# NT_SolarModule2.net
KiCad netlist of a schematic drawn in EAGLE
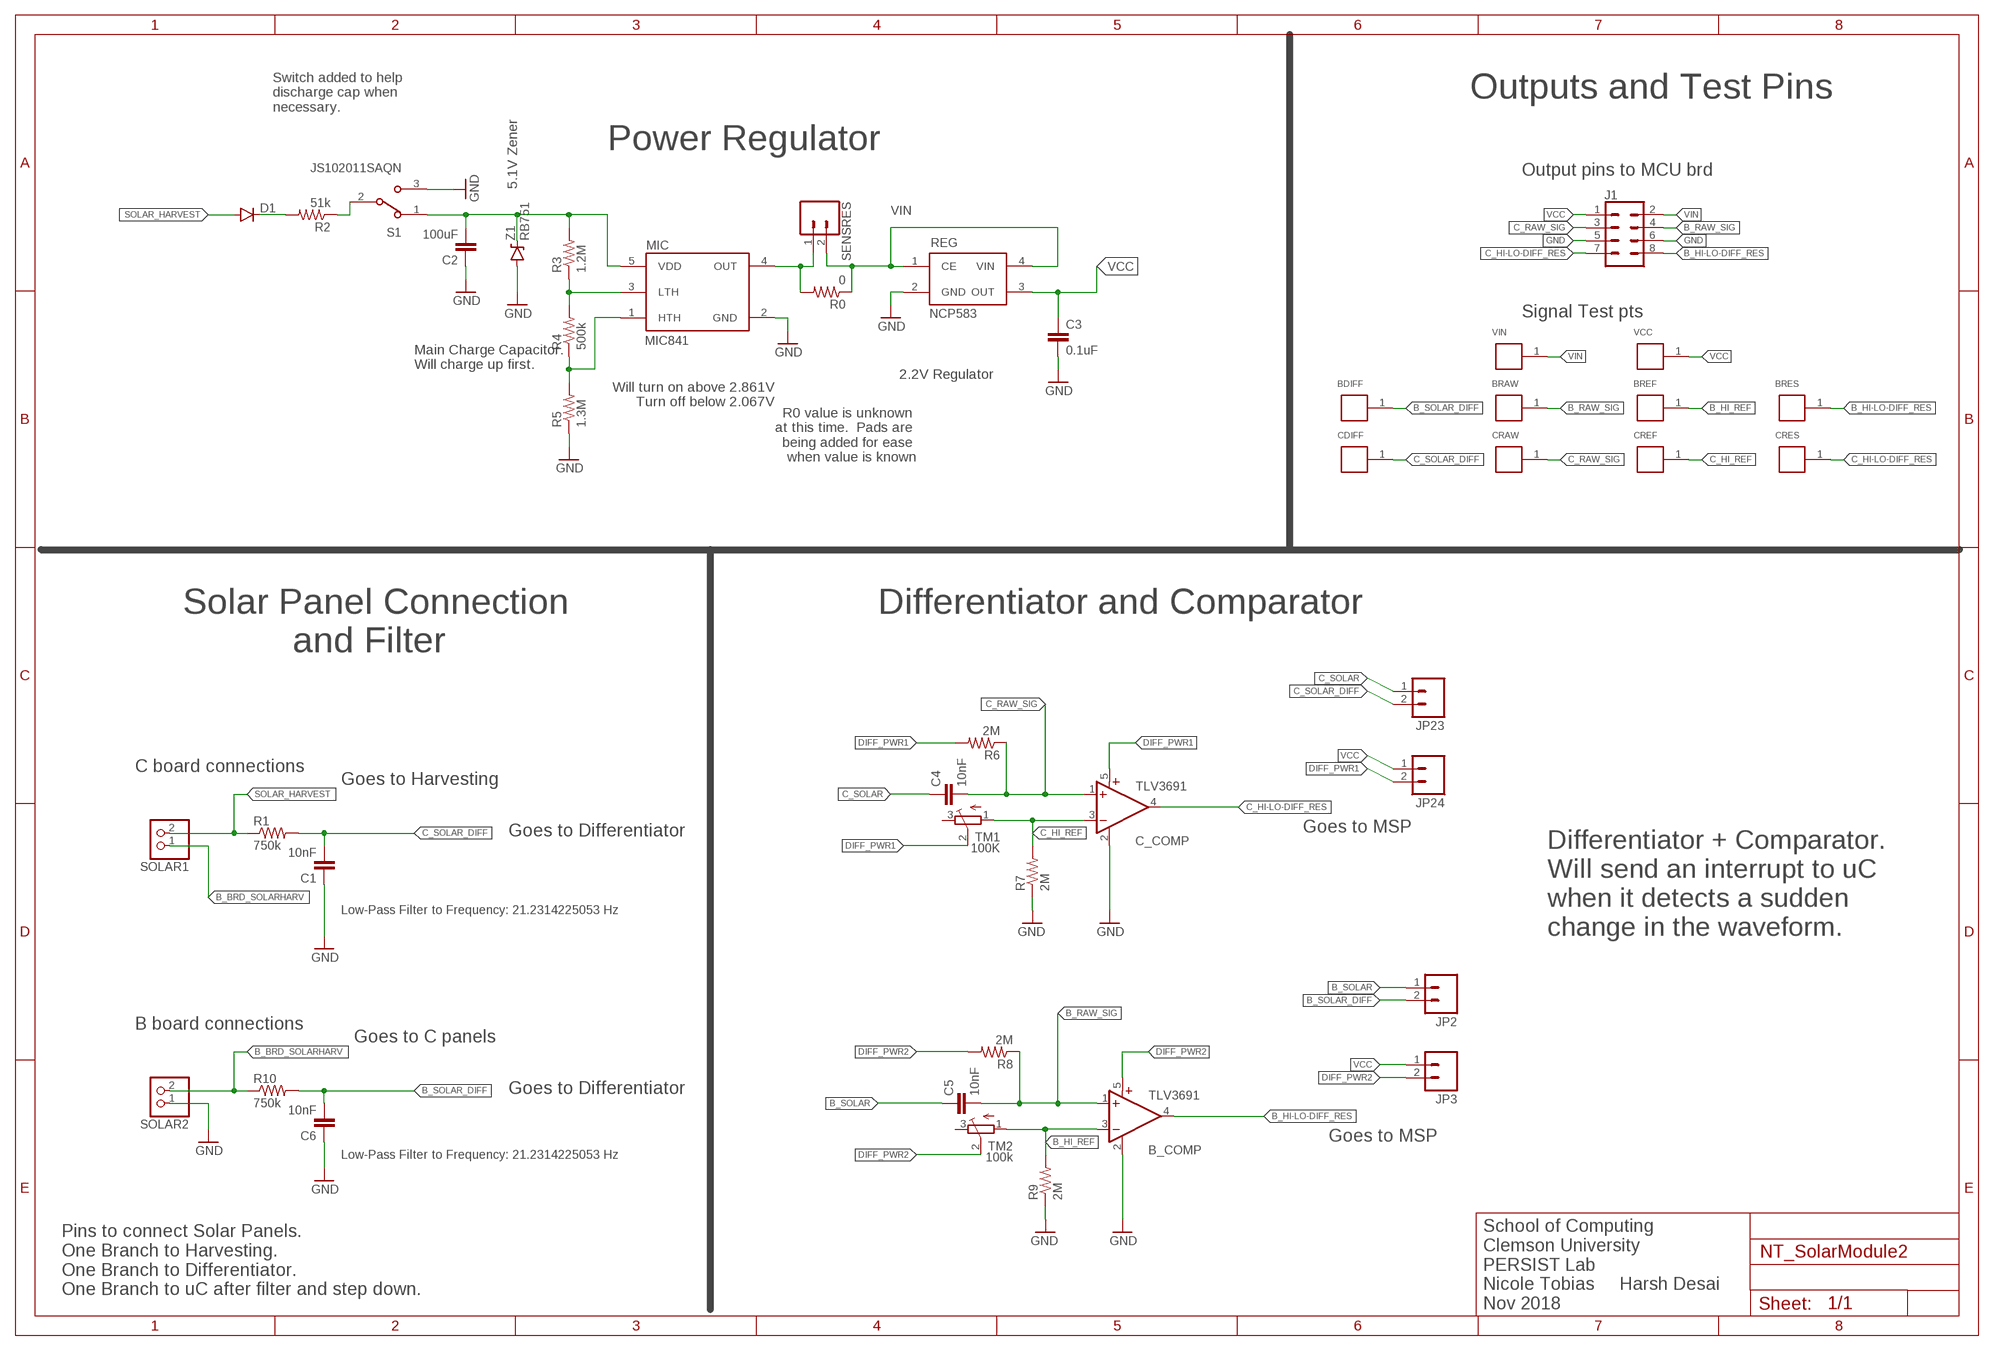
[diagram p0: schematic, sheet 1]

(export (version "E")
  (design (tool "Eeschema 10.0.6"))
  (components
    (comp (ref "BDIFF")
      (value "RCU-0C")
      (footprint "eagle-import:TE_RCU-0C")
      (fields
        (field (name "COMMENT") "RCU-0C _1625854-3_")
        (field (name "MF") "TE Connectivity")
        (field (name "TOLERANCE") "0%")
      )
      (libsource (lib "eagle-import") (part "RCU-0C"))
    )
    (comp (ref "BRAW")
      (value "RCU-0C")
      (footprint "eagle-import:TE_RCU-0C")
      (fields
        (field (name "COMMENT") "RCU-0C _1625854-3_")
        (field (name "MF") "TE Connectivity")
        (field (name "TOLERANCE") "0%")
      )
      (libsource (lib "eagle-import") (part "RCU-0C"))
    )
    (comp (ref "BREF")
      (value "RCU-0C")
      (footprint "eagle-import:TE_RCU-0C")
      (fields
        (field (name "COMMENT") "RCU-0C _1625854-3_")
        (field (name "MF") "TE Connectivity")
        (field (name "TOLERANCE") "0%")
      )
      (libsource (lib "eagle-import") (part "RCU-0C"))
    )
    (comp (ref "BRES")
      (value "RCU-0C")
      (footprint "eagle-import:TE_RCU-0C")
      (fields
        (field (name "COMMENT") "RCU-0C _1625854-3_")
        (field (name "MF") "TE Connectivity")
        (field (name "TOLERANCE") "0%")
      )
      (libsource (lib "eagle-import") (part "RCU-0C"))
    )
    (comp (ref "B_COMP")
      (value "TLV3691")
      (footprint "eagle-import:SC70-5")
      (libsource (lib "eagle-import") (part "TLV3691"))
    )
    (comp (ref "C1")
      (value "10nF")
      (footprint "eagle-import:0603-CAP")
      (libsource (lib "eagle-import") (part "CAP0603-CAP"))
    )
    (comp (ref "C2")
      (value "100uF")
      (footprint "eagle-import:0603-CAP")
      (libsource (lib "eagle-import") (part "CAP0603-CAP"))
    )
    (comp (ref "C3")
      (value "0.1uF")
      (footprint "eagle-import:0603-CAP")
      (libsource (lib "eagle-import") (part "CAP0603-CAP"))
    )
    (comp (ref "C4")
      (value "10nF")
      (footprint "eagle-import:0603-CAP")
      (libsource (lib "eagle-import") (part "CAP0603-CAP"))
    )
    (comp (ref "C5")
      (value "10nF")
      (footprint "eagle-import:0603-CAP")
      (libsource (lib "eagle-import") (part "CAP0603-CAP"))
    )
    (comp (ref "C6")
      (value "10nF")
      (footprint "eagle-import:0603-CAP")
      (libsource (lib "eagle-import") (part "CAP0603-CAP"))
    )
    (comp (ref "CDIFF")
      (value "RCU-0C")
      (footprint "eagle-import:TE_RCU-0C")
      (fields
        (field (name "COMMENT") "RCU-0C _1625854-3_")
        (field (name "MF") "TE Connectivity")
        (field (name "TOLERANCE") "0%")
      )
      (libsource (lib "eagle-import") (part "RCU-0C"))
    )
    (comp (ref "CRAW")
      (value "RCU-0C")
      (footprint "eagle-import:TE_RCU-0C")
      (fields
        (field (name "COMMENT") "RCU-0C _1625854-3_")
        (field (name "MF") "TE Connectivity")
        (field (name "TOLERANCE") "0%")
      )
      (libsource (lib "eagle-import") (part "RCU-0C"))
    )
    (comp (ref "CREF")
      (value "RCU-0C")
      (footprint "eagle-import:TE_RCU-0C")
      (fields
        (field (name "COMMENT") "RCU-0C _1625854-3_")
        (field (name "MF") "TE Connectivity")
        (field (name "TOLERANCE") "0%")
      )
      (libsource (lib "eagle-import") (part "RCU-0C"))
    )
    (comp (ref "CRES")
      (value "RCU-0C")
      (footprint "eagle-import:TE_RCU-0C")
      (fields
        (field (name "COMMENT") "RCU-0C _1625854-3_")
        (field (name "MF") "TE Connectivity")
        (field (name "TOLERANCE") "0%")
      )
      (libsource (lib "eagle-import") (part "RCU-0C"))
    )
    (comp (ref "C_COMP")
      (value "TLV3691")
      (footprint "eagle-import:SC70-5")
      (libsource (lib "eagle-import") (part "TLV3691"))
    )
    (comp (ref "D1")
      (value "DIODESOD523")
      (footprint "eagle-import:SOD523")
      (libsource (lib "eagle-import") (part "DIODESOD523"))
    )
    (comp (ref "J1")
      (value "CONN_04X2")
      (footprint "eagle-import:2X4")
      (libsource (lib "eagle-import") (part "CONN_04X2"))
    )
    (comp (ref "JP2")
      (value "M02")
      (footprint "eagle-import:1X02-1.27MM")
      (libsource (lib "eagle-import") (part "M02"))
    )
    (comp (ref "JP3")
      (value "M02")
      (footprint "eagle-import:1X02-1.27MM")
      (libsource (lib "eagle-import") (part "M02"))
    )
    (comp (ref "JP23")
      (value "M02")
      (footprint "eagle-import:1X02-1.27MM")
      (libsource (lib "eagle-import") (part "M02"))
    )
    (comp (ref "JP24")
      (value "M02")
      (footprint "eagle-import:1X02-1.27MM")
      (libsource (lib "eagle-import") (part "M02"))
    )
    (comp (ref "MIC")
      (value "MIC841")
      (footprint "eagle-import:SC70-5")
      (libsource (lib "eagle-import") (part "MIC841"))
    )
    (comp (ref "R0")
      (value "0")
      (footprint "eagle-import:0603-RES")
      (libsource (lib "eagle-import") (part "RESISTOR0603"))
    )
    (comp (ref "R1")
      (value "750k")
      (footprint "eagle-import:0603-RES")
      (libsource (lib "eagle-import") (part "RESISTOR0603"))
    )
    (comp (ref "R2")
      (value "51k")
      (footprint "eagle-import:0603-RES")
      (libsource (lib "eagle-import") (part "RESISTOR0603"))
    )
    (comp (ref "R3")
      (value "1.2M")
      (footprint "eagle-import:0603-RES")
      (libsource (lib "eagle-import") (part "RESISTOR0603"))
    )
    (comp (ref "R4")
      (value "500k")
      (footprint "eagle-import:0603-RES")
      (libsource (lib "eagle-import") (part "RESISTOR0603"))
    )
    (comp (ref "R5")
      (value "1.3M")
      (footprint "eagle-import:0603-RES")
      (libsource (lib "eagle-import") (part "RESISTOR0603"))
    )
    (comp (ref "R6")
      (value "2M")
      (footprint "eagle-import:0603-RES")
      (libsource (lib "eagle-import") (part "RESISTOR0603"))
    )
    (comp (ref "R7")
      (value "2M")
      (footprint "eagle-import:0603-RES")
      (libsource (lib "eagle-import") (part "RESISTOR0603"))
    )
    (comp (ref "R8")
      (value "2M")
      (footprint "eagle-import:0603-RES")
      (libsource (lib "eagle-import") (part "RESISTOR0603"))
    )
    (comp (ref "R9")
      (value "2M")
      (footprint "eagle-import:0603-RES")
      (libsource (lib "eagle-import") (part "RESISTOR0603"))
    )
    (comp (ref "R10")
      (value "750k")
      (footprint "eagle-import:0603-RES")
      (libsource (lib "eagle-import") (part "RESISTOR0603"))
    )
    (comp (ref "REG")
      (value "NCP583")
      (footprint "eagle-import:SC82-AB_1PRIMARY")
      (libsource (lib "eagle-import") (part "NCP583"))
    )
    (comp (ref "S1")
      (value "JS102011SAQN")
      (footprint "eagle-import:SW_JS102011SAQN")
      (fields (field (name "MF") "C&K Components"))
      (libsource (lib "eagle-import") (part "JS102011SAQN"))
    )
    (comp (ref "SENSRES")
      (value "CONN_02")
      (footprint "eagle-import:1X02")
      (libsource (lib "eagle-import") (part "CONN_02"))
    )
    (comp (ref "SOLAR1")
      (value "PINHD-1X2")
      (footprint "eagle-import:1X02")
      (libsource (lib "eagle-import") (part "PINHD-1X2"))
    )
    (comp (ref "SOLAR2")
      (value "PINHD-1X2")
      (footprint "eagle-import:1X02")
      (libsource (lib "eagle-import") (part "PINHD-1X2"))
    )
    (comp (ref "TM1")
      (value "100K")
      (footprint "eagle-import:TC33X")
      (libsource (lib "eagle-import") (part "TRIMPOTTC33X"))
    )
    (comp (ref "TM2")
      (value "100k")
      (footprint "eagle-import:TC33X")
      (libsource (lib "eagle-import") (part "TRIMPOTTC33X"))
    )
    (comp (ref "VCC")
      (value "RCU-0C")
      (footprint "eagle-import:TE_RCU-0C")
      (fields
        (field (name "COMMENT") "RCU-0C _1625854-3_")
        (field (name "MF") "TE Connectivity")
        (field (name "TOLERANCE") "0%")
      )
      (libsource (lib "eagle-import") (part "RCU-0C"))
    )
    (comp (ref "VIN")
      (value "RCU-0C")
      (footprint "eagle-import:TE_RCU-0C")
      (fields
        (field (name "COMMENT") "RCU-0C _1625854-3_")
        (field (name "MF") "TE Connectivity")
        (field (name "TOLERANCE") "0%")
      )
      (libsource (lib "eagle-import") (part "RCU-0C"))
    )
    (comp (ref "Z1")
      (value "RB751")
      (footprint "eagle-import:SOD-523")
      (libsource (lib "eagle-import") (part "DIODE-ZENER"))
    )
  )
  (nets
    (net (code "1") (name "B_BRD_SOLARHARV") (class "Default")
      (node (ref "R10") (pin "1") (pinfunction "1_1") (pintype "passive"))
      (node (ref "SOLAR1") (pin "1") (pinfunction "1_1") (pintype "passive"))
      (node (ref "SOLAR2") (pin "2") (pinfunction "2_2") (pintype "passive"))
    )
    (net (code "2") (name "B_HI-LO-DIFF_RES") (class "Default")
      (node (ref "BRES") (pin "1") (pinfunction "1_1") (pintype "passive"))
      (node (ref "B_COMP") (pin "4") (pinfunction "OUT_4") (pintype "output"))
      (node (ref "J1") (pin "8") (pinfunction "8_8") (pintype "passive"))
    )
    (net (code "3") (name "B_HI_REF") (class "Default")
      (node (ref "BREF") (pin "1") (pinfunction "1_1") (pintype "passive"))
      (node (ref "B_COMP") (pin "3") (pinfunction "-IN_3") (pintype "input"))
      (node (ref "R9") (pin "2") (pinfunction "2_2") (pintype "passive"))
      (node (ref "TM2") (pin "1") (pinfunction "A_1") (pintype "passive"))
    )
    (net (code "4") (name "B_RAW_SIG") (class "Default")
      (node (ref "BRAW") (pin "1") (pinfunction "1_1") (pintype "passive"))
      (node (ref "B_COMP") (pin "1") (pinfunction "+IN_1") (pintype "input"))
      (node (ref "C5") (pin "2") (pinfunction "2_2") (pintype "passive"))
      (node (ref "J1") (pin "4") (pinfunction "4_4") (pintype "passive"))
      (node (ref "R8") (pin "1") (pinfunction "1_1") (pintype "passive"))
    )
    (net (code "5") (name "B_SOLAR") (class "Default")
      (node (ref "C5") (pin "1") (pinfunction "1_1") (pintype "passive"))
      (node (ref "JP2") (pin "1") (pinfunction "1_1") (pintype "passive"))
    )
    (net (code "6") (name "B_SOLAR_DIFF") (class "Default")
      (node (ref "BDIFF") (pin "1") (pinfunction "1_1") (pintype "passive"))
      (node (ref "C6") (pin "2") (pinfunction "2_2") (pintype "passive"))
      (node (ref "JP2") (pin "2") (pinfunction "2_2") (pintype "passive"))
      (node (ref "R10") (pin "2") (pinfunction "2_2") (pintype "passive"))
    )
    (net (code "7") (name "C_HI-LO-DIFF_RES") (class "Default")
      (node (ref "CRES") (pin "1") (pinfunction "1_1") (pintype "passive"))
      (node (ref "C_COMP") (pin "4") (pinfunction "OUT_4") (pintype "output"))
      (node (ref "J1") (pin "7") (pinfunction "7_7") (pintype "passive"))
    )
    (net (code "8") (name "C_HI_REF") (class "Default")
      (node (ref "CREF") (pin "1") (pinfunction "1_1") (pintype "passive"))
      (node (ref "C_COMP") (pin "3") (pinfunction "-IN_3") (pintype "input"))
      (node (ref "R7") (pin "2") (pinfunction "2_2") (pintype "passive"))
      (node (ref "TM1") (pin "1") (pinfunction "A_1") (pintype "passive"))
    )
    (net (code "9") (name "C_RAW_SIG") (class "Default")
      (node (ref "C4") (pin "2") (pinfunction "2_2") (pintype "passive"))
      (node (ref "CRAW") (pin "1") (pinfunction "1_1") (pintype "passive"))
      (node (ref "C_COMP") (pin "1") (pinfunction "+IN_1") (pintype "input"))
      (node (ref "J1") (pin "3") (pinfunction "3_3") (pintype "passive"))
      (node (ref "R6") (pin "1") (pinfunction "1_1") (pintype "passive"))
    )
    (net (code "10") (name "C_SOLAR") (class "Default")
      (node (ref "C4") (pin "1") (pinfunction "1_1") (pintype "passive"))
      (node (ref "JP23") (pin "1") (pinfunction "1_1") (pintype "passive"))
    )
    (net (code "11") (name "C_SOLAR_DIFF") (class "Default")
      (node (ref "C1") (pin "2") (pinfunction "2_2") (pintype "passive"))
      (node (ref "CDIFF") (pin "1") (pinfunction "1_1") (pintype "passive"))
      (node (ref "JP23") (pin "2") (pinfunction "2_2") (pintype "passive"))
      (node (ref "R1") (pin "2") (pinfunction "2_2") (pintype "passive"))
    )
    (net (code "12") (name "DIFF_PWR1") (class "Default")
      (node (ref "C_COMP") (pin "5") (pinfunction "V+_5") (pintype "power_in"))
      (node (ref "JP24") (pin "2") (pinfunction "2_2") (pintype "passive"))
      (node (ref "R6") (pin "2") (pinfunction "2_2") (pintype "passive"))
      (node (ref "TM1") (pin "2") (pinfunction "S_2") (pintype "passive"))
    )
    (net (code "13") (name "DIFF_PWR2") (class "Default")
      (node (ref "B_COMP") (pin "5") (pinfunction "V+_5") (pintype "power_in"))
      (node (ref "JP3") (pin "2") (pinfunction "2_2") (pintype "passive"))
      (node (ref "R8") (pin "2") (pinfunction "2_2") (pintype "passive"))
      (node (ref "TM2") (pin "2") (pinfunction "S_2") (pintype "passive"))
    )
    (net (code "14") (name "GND") (class "Default")
      (node (ref "B_COMP") (pin "2") (pinfunction "GND_2") (pintype "power_in"))
      (node (ref "C1") (pin "1") (pinfunction "1_1") (pintype "passive"))
      (node (ref "C2") (pin "1") (pinfunction "1_1") (pintype "passive"))
      (node (ref "C3") (pin "2") (pinfunction "2_2") (pintype "passive"))
      (node (ref "C6") (pin "1") (pinfunction "1_1") (pintype "passive"))
      (node (ref "C_COMP") (pin "2") (pinfunction "GND_2") (pintype "power_in"))
      (node (ref "J1") (pin "5") (pinfunction "5_5") (pintype "passive"))
      (node (ref "J1") (pin "6") (pinfunction "6_6") (pintype "passive"))
      (node (ref "MIC") (pin "2") (pinfunction "GND_2") (pintype "bidirectional"))
      (node (ref "R5") (pin "1") (pinfunction "1_1") (pintype "passive"))
      (node (ref "R7") (pin "1") (pinfunction "1_1") (pintype "passive"))
      (node (ref "R9") (pin "1") (pinfunction "1_1") (pintype "passive"))
      (node (ref "REG") (pin "2") (pinfunction "GND_2") (pintype "bidirectional"))
      (node (ref "S1") (pin "3") (pinfunction "3_3") (pintype "passive"))
      (node (ref "SOLAR2") (pin "1") (pinfunction "1_1") (pintype "passive"))
      (node (ref "Z1") (pin "ANODE") (pinfunction "A_ANODE") (pintype "passive"))
    )
    (net (code "15") (name "Net-(D1-PadC)") (class "Default")
      (node (ref "D1") (pin "C") (pinfunction "C_C") (pintype "passive"))
      (node (ref "R2") (pin "2") (pinfunction "2_2") (pintype "passive"))
    )
    (net (code "16") (name "Net-(MIC-HTH)") (class "Default")
      (node (ref "MIC") (pin "1") (pinfunction "HTH_1") (pintype "bidirectional"))
      (node (ref "R4") (pin "1") (pinfunction "1_1") (pintype "passive"))
      (node (ref "R5") (pin "2") (pinfunction "2_2") (pintype "passive"))
    )
    (net (code "17") (name "Net-(MIC-LTH)") (class "Default")
      (node (ref "MIC") (pin "3") (pinfunction "LTH_3") (pintype "bidirectional"))
      (node (ref "R3") (pin "1") (pinfunction "1_1") (pintype "passive"))
      (node (ref "R4") (pin "2") (pinfunction "2_2") (pintype "passive"))
    )
    (net (code "18") (name "Net-(MIC-OUT)") (class "Default")
      (node (ref "MIC") (pin "4") (pinfunction "OUT_4") (pintype "bidirectional"))
      (node (ref "R0") (pin "2") (pinfunction "2_2") (pintype "passive"))
      (node (ref "SENSRES") (pin "1") (pinfunction "1_1") (pintype "passive"))
    )
    (net (code "19") (name "Net-(MIC-VDD)") (class "Default")
      (node (ref "C2") (pin "2") (pinfunction "2_2") (pintype "passive"))
      (node (ref "MIC") (pin "5") (pinfunction "VDD_5") (pintype "bidirectional"))
      (node (ref "R3") (pin "2") (pinfunction "2_2") (pintype "passive"))
      (node (ref "S1") (pin "1") (pinfunction "1_1") (pintype "passive"))
      (node (ref "Z1") (pin "CATHODE") (pinfunction "C_CATHODE") (pintype "passive"))
    )
    (net (code "20") (name "Net-(R2-Pad1)") (class "Default")
      (node (ref "R2") (pin "1") (pinfunction "1_1") (pintype "passive"))
      (node (ref "S1") (pin "2") (pinfunction "2_2") (pintype "passive"))
    )
    (net (code "21") (name "SOLAR_HARVEST") (class "Default")
      (node (ref "D1") (pin "A") (pinfunction "A_A") (pintype "passive"))
      (node (ref "R1") (pin "1") (pinfunction "1_1") (pintype "passive"))
      (node (ref "SOLAR1") (pin "2") (pinfunction "2_2") (pintype "passive"))
    )
    (net (code "22") (name "VCC") (class "Default")
      (node (ref "C3") (pin "1") (pinfunction "1_1") (pintype "passive"))
      (node (ref "J1") (pin "1") (pinfunction "1_1") (pintype "passive"))
      (node (ref "JP24") (pin "1") (pinfunction "1_1") (pintype "passive"))
      (node (ref "JP3") (pin "1") (pinfunction "1_1") (pintype "passive"))
      (node (ref "REG") (pin "3") (pinfunction "OUT_3") (pintype "bidirectional"))
      (node (ref "VCC") (pin "1") (pinfunction "1_1") (pintype "passive"))
    )
    (net (code "23") (name "VIN") (class "Default")
      (node (ref "J1") (pin "2") (pinfunction "2_2") (pintype "passive"))
      (node (ref "R0") (pin "1") (pinfunction "1_1") (pintype "passive"))
      (node (ref "REG") (pin "1") (pinfunction "CE_1") (pintype "bidirectional"))
      (node (ref "REG") (pin "4") (pinfunction "VIN_4") (pintype "bidirectional"))
      (node (ref "SENSRES") (pin "2") (pinfunction "2_2") (pintype "passive"))
      (node (ref "VIN") (pin "1") (pinfunction "1_1") (pintype "passive"))
    )
    (net (code "24") (name "unconnected-(TM1-E-Pad3)") (class "Default")
      (node (ref "TM1") (pin "3") (pinfunction "E_3") (pintype "passive"))
    )
    (net (code "25") (name "unconnected-(TM2-E-Pad3)") (class "Default")
      (node (ref "TM2") (pin "3") (pinfunction "E_3") (pintype "passive"))
    )
  )
)
